# easyeda.net
KiCad netlist of a schematic drawn in EasyEDA
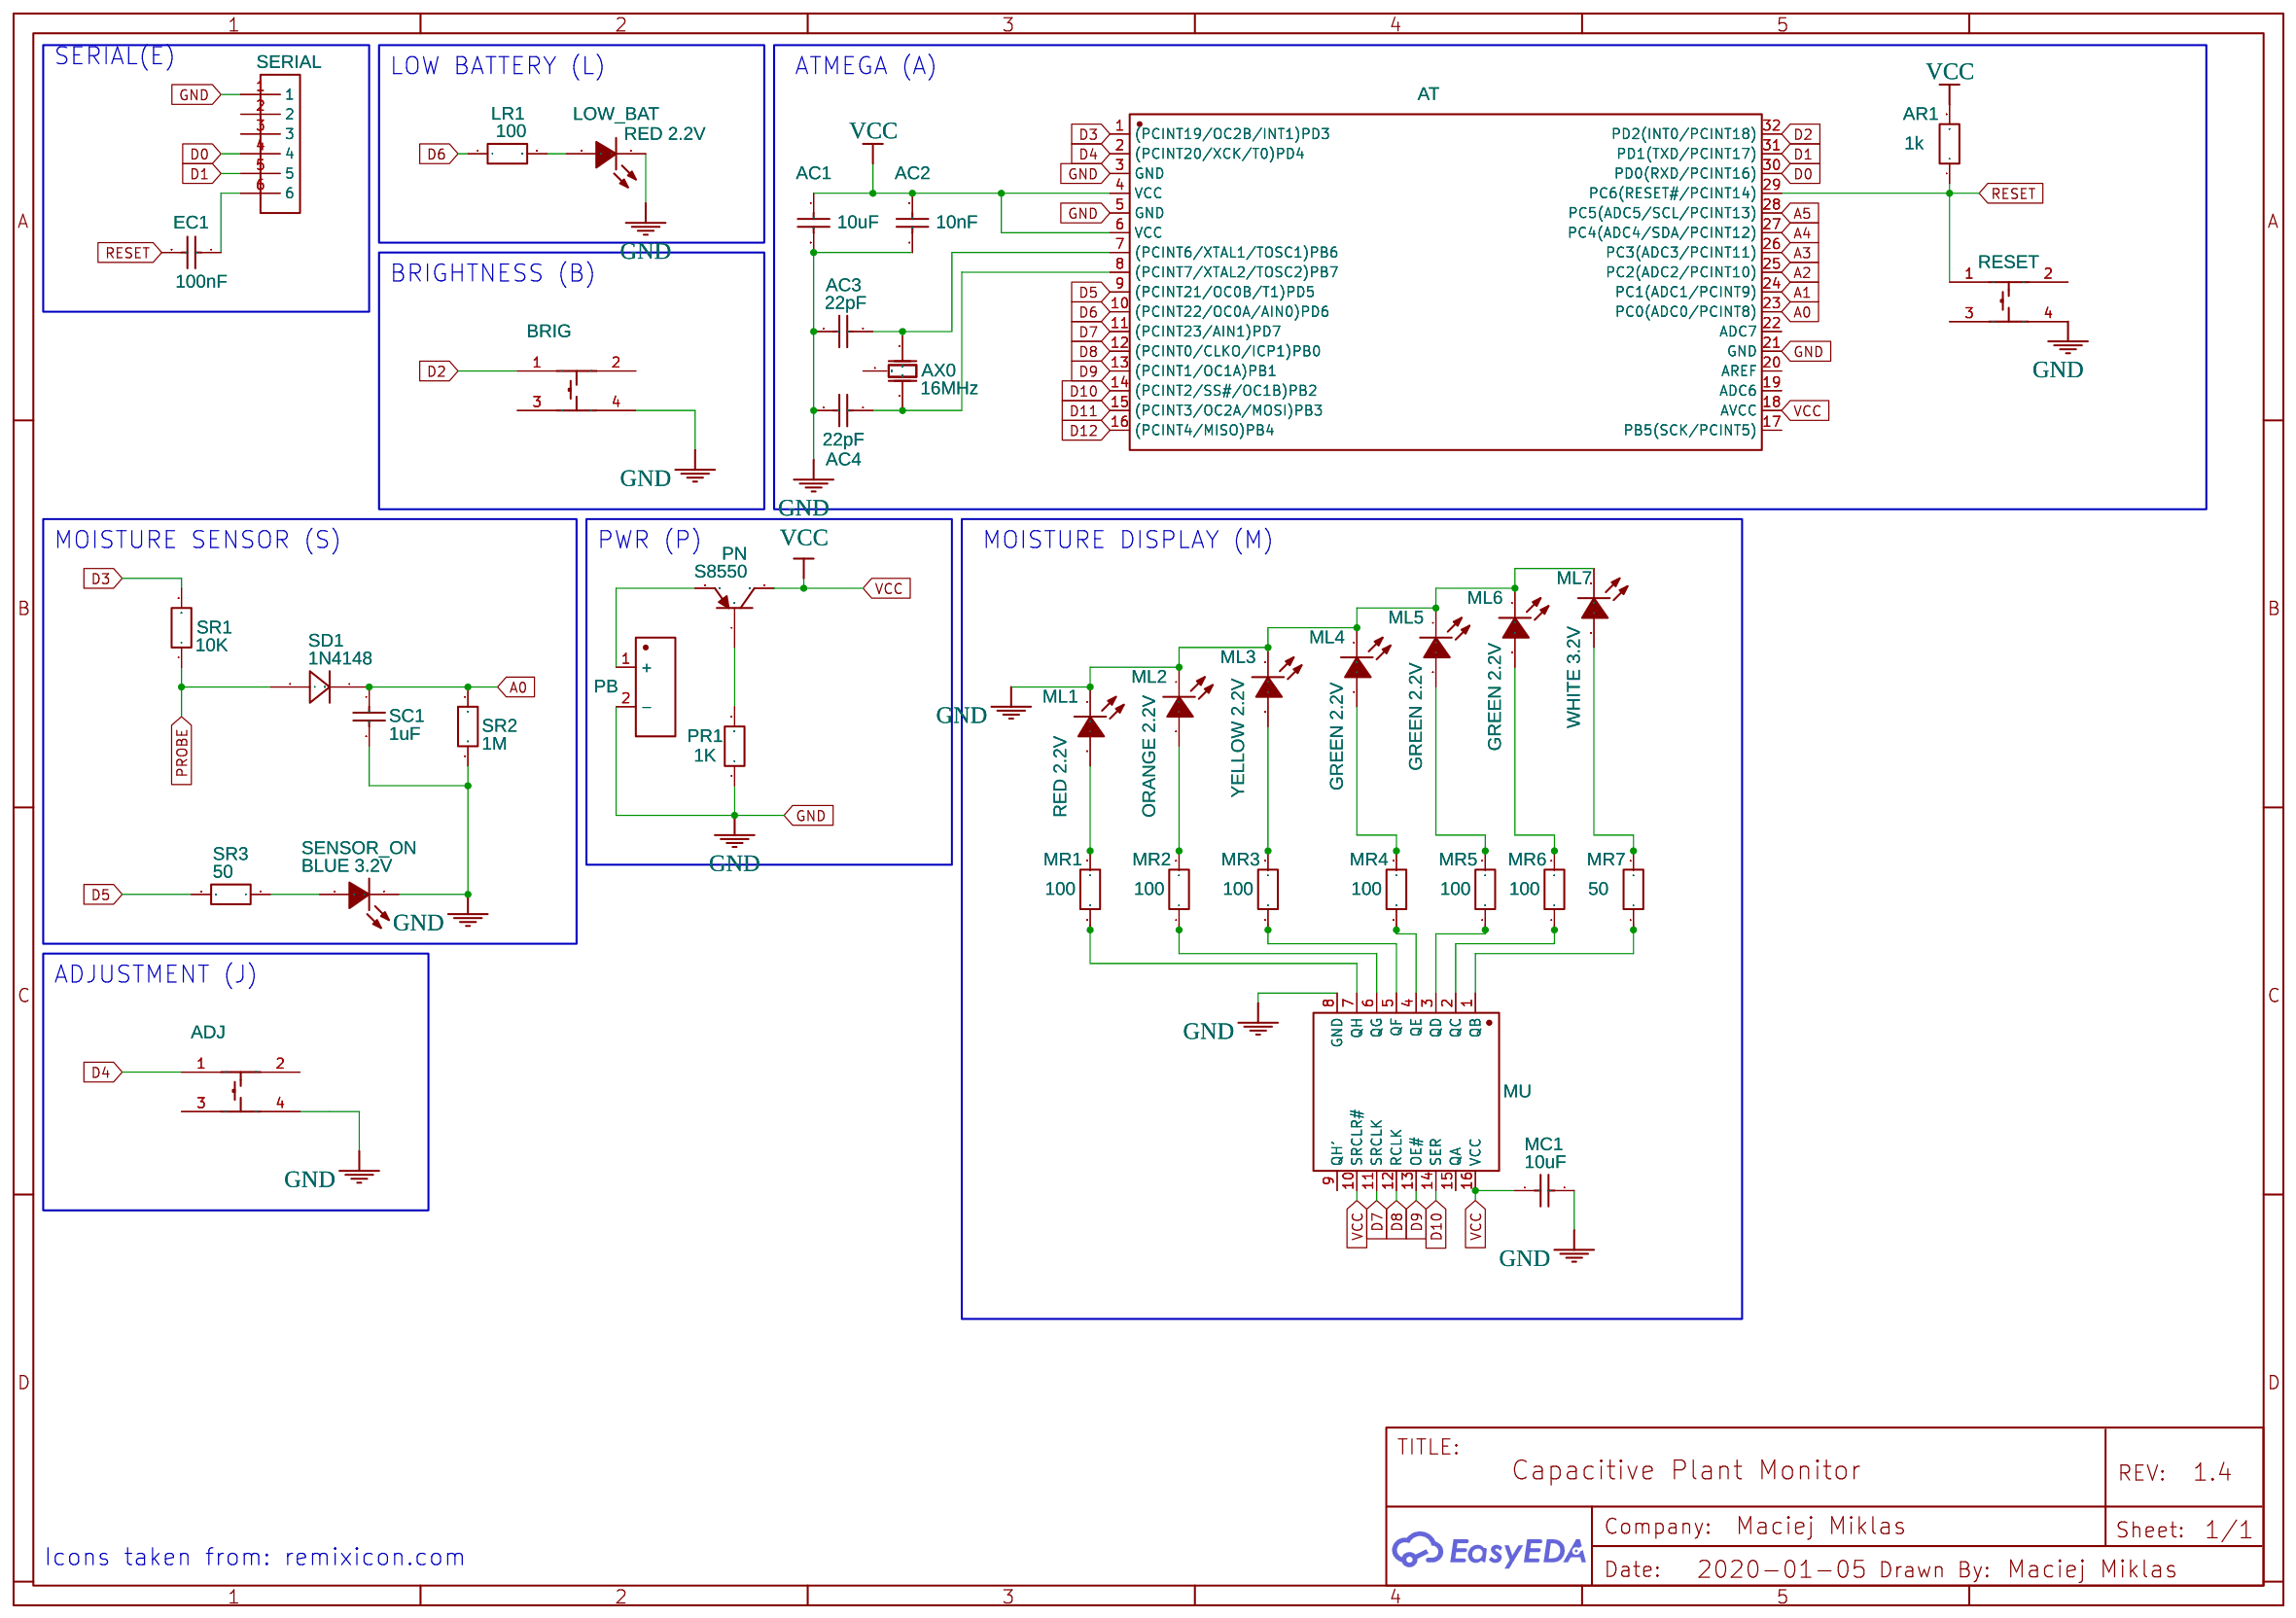
[diagram p0: schematic sheet]

(export (version "E")
  (design (tool "Eeschema 10.0.6"))
  (components
    (comp (ref "AC1")
      (value "10uF")
      (fields (field (name "Manufacturer Part") "CC0805KKX7R9BB105") (field (name "Manufacturer") "YAGEO"))
      (libsource (lib "") (part "CC0805KKX7R9BB105_1"))
    )
    (comp (ref "AC2")
      (value "10nF")
      (fields (field (name "Manufacturer Part") "CC0805KKX7R9BB105") (field (name "Manufacturer") "YAGEO"))
      (libsource (lib "") (part "CC0805KKX7R9BB105_1"))
    )
    (comp (ref "AC3")
      (value "22pF")
      (fields (field (name "Manufacturer Part") "CC0805KKX7R9BB105") (field (name "Manufacturer") "YAGEO"))
      (libsource (lib "") (part "CC0805KKX7R9BB105_2"))
    )
    (comp (ref "AC4")
      (value "22pF")
      (fields (field (name "Manufacturer Part") "CC0805KKX7R9BB105") (field (name "Manufacturer") "YAGEO"))
      (libsource (lib "") (part "CC0805KKX7R9BB105_2"))
    )
    (comp (ref "ADJ") (value "Push Button") (libsource (lib "") (part "Push Button")))
    (comp (ref "AR1")
      (value "1k")
      (fields
        (field (name "Manufacturer Part") "WR08X102 JTL")
        (field (name "Manufacturer") "Walsin Tech Corp")
      )
      (libsource (lib "") (part "WR08X102 JTL_2"))
    )
    (comp (ref "AT")
      (value "ATMEGA328P-AU")
      (fields (field (name "Manufacturer") "MICROCHIP"))
      (libsource (lib "") (part "ATMEGA328P-AU"))
    )
    (comp (ref "AX0")
      (value "16MHz")
      (fields
        (field (name "Manufacturer Part") "CSTNE16M0V530000R0")
        (field (name "Manufacturer") "Murata Electronics")
      )
      (libsource (lib "") (part "CSTNE16M0V530000R0"))
    )
    (comp (ref "BRIG") (value "Push Button") (libsource (lib "") (part "Push Button_2")))
    (comp (ref "EC1")
      (value "100nF")
      (fields (field (name "Manufacturer Part") "CC0805KKX7R9BB105") (field (name "Manufacturer") "YAGEO"))
      (libsource (lib "") (part "CC0805KKX7R9BB105"))
    )
    (comp (ref "LOW_BAT")
      (value "RED 2.2V")
      (fields
        (field (name "Manufacturer Part") "FC-1608YOXK-600H08")
        (field (name "Manufacturer") "NATIONSTAR")
      )
      (libsource (lib "") (part "FC-1608YOXK-600H08_1"))
    )
    (comp (ref "LR1")
      (value "100")
      (fields
        (field (name "Manufacturer Part") "WR08X102 JTL")
        (field (name "Manufacturer") "Walsin Tech Corp")
      )
      (libsource (lib "") (part "WR08X102 JTL_6"))
    )
    (comp (ref "MC1")
      (value "10uF")
      (fields (field (name "Manufacturer Part") "CC0805KKX7R9BB105") (field (name "Manufacturer") "YAGEO"))
      (libsource (lib "") (part "CC0805KKX7R9BB105_4"))
    )
    (comp (ref "ML1")
      (value "RED 2.2V")
      (fields
        (field (name "Manufacturer Part") "FC-1608YOXK-600H08")
        (field (name "Manufacturer") "NATIONSTAR")
      )
      (libsource (lib "") (part "FC-1608YOXK-600H08"))
    )
    (comp (ref "ML2")
      (value "ORANGE 2.2V")
      (fields
        (field (name "Manufacturer Part") "FC-1608YOXK-600H08")
        (field (name "Manufacturer") "NATIONSTAR")
      )
      (libsource (lib "") (part "FC-1608YOXK-600H08"))
    )
    (comp (ref "ML3")
      (value "YELLOW 2.2V")
      (fields
        (field (name "Manufacturer Part") "FC-1608YOXK-600H08")
        (field (name "Manufacturer") "NATIONSTAR")
      )
      (libsource (lib "") (part "FC-1608YOXK-600H08"))
    )
    (comp (ref "ML4")
      (value "GREEN 2.2V")
      (fields
        (field (name "Manufacturer Part") "FC-1608YOXK-600H08")
        (field (name "Manufacturer") "NATIONSTAR")
      )
      (libsource (lib "") (part "FC-1608YOXK-600H08"))
    )
    (comp (ref "ML5")
      (value "GREEN 2.2V")
      (fields
        (field (name "Manufacturer Part") "FC-1608YOXK-600H08")
        (field (name "Manufacturer") "NATIONSTAR")
      )
      (libsource (lib "") (part "FC-1608YOXK-600H08"))
    )
    (comp (ref "ML6")
      (value "GREEN 2.2V")
      (fields
        (field (name "Manufacturer Part") "FC-1608YOXK-600H08")
        (field (name "Manufacturer") "NATIONSTAR")
      )
      (libsource (lib "") (part "FC-1608YOXK-600H08"))
    )
    (comp (ref "ML7")
      (value "WHITE 3.2V")
      (fields
        (field (name "Manufacturer Part") "FC-1608YOXK-600H08")
        (field (name "Manufacturer") "NATIONSTAR")
      )
      (libsource (lib "") (part "FC-1608YOXK-600H08"))
    )
    (comp (ref "MR1")
      (value "100")
      (fields
        (field (name "Manufacturer Part") "WR08X102 JTL")
        (field (name "Manufacturer") "Walsin Tech Corp")
      )
      (libsource (lib "") (part "WR08X102 JTL_1"))
    )
    (comp (ref "MR2")
      (value "100")
      (fields
        (field (name "Manufacturer Part") "WR08X102 JTL")
        (field (name "Manufacturer") "Walsin Tech Corp")
      )
      (libsource (lib "") (part "WR08X102 JTL_1"))
    )
    (comp (ref "MR3")
      (value "100")
      (fields
        (field (name "Manufacturer Part") "WR08X102 JTL")
        (field (name "Manufacturer") "Walsin Tech Corp")
      )
      (libsource (lib "") (part "WR08X102 JTL_1"))
    )
    (comp (ref "MR4")
      (value "100")
      (fields
        (field (name "Manufacturer Part") "WR08X102 JTL")
        (field (name "Manufacturer") "Walsin Tech Corp")
      )
      (libsource (lib "") (part "WR08X102 JTL_1"))
    )
    (comp (ref "MR5")
      (value "100")
      (fields
        (field (name "Manufacturer Part") "WR08X102 JTL")
        (field (name "Manufacturer") "Walsin Tech Corp")
      )
      (libsource (lib "") (part "WR08X102 JTL_1"))
    )
    (comp (ref "MR6")
      (value "100")
      (fields
        (field (name "Manufacturer Part") "WR08X102 JTL")
        (field (name "Manufacturer") "Walsin Tech Corp")
      )
      (libsource (lib "") (part "WR08X102 JTL_1"))
    )
    (comp (ref "MR7")
      (value "50")
      (fields
        (field (name "Manufacturer Part") "WR08X102 JTL")
        (field (name "Manufacturer") "Walsin Tech Corp")
      )
      (libsource (lib "") (part "WR08X102 JTL_1"))
    )
    (comp (ref "MU")
      (value "CD74HC595M96")
      (fields (field (name "Manufacturer") "TI"))
      (libsource (lib "") (part "CD74HC595M96"))
    )
    (comp (ref "PB")
      (value "‎BK-18650-PC2‎")
      (fields
        (field (name "Manufacturer Part") "BK-18650-PC2")
        (field (name "Manufacturer") "MPD (Memory Protection Devices)")
      )
      (libsource (lib "") (part "‎BK-18650-PC2‎"))
    )
    (comp (ref "PN")
      (value "S8550")
      (fields (field (name "Manufacturer") "CBI(创基)"))
      (libsource (lib "") (part "S8550_C2828467"))
    )
    (comp (ref "PR1")
      (value "1K")
      (fields
        (field (name "Manufacturer Part") "WR08X102 JTL")
        (field (name "Manufacturer") "Walsin Tech Corp")
      )
      (libsource (lib "") (part "WR08X102 JTL_3"))
    )
    (comp (ref "RESET") (value "Push Button") (libsource (lib "") (part "Push Button_1")))
    (comp (ref "SC1")
      (value "1uF")
      (fields (field (name "Manufacturer Part") "CC0805KKX7R9BB105") (field (name "Manufacturer") "YAGEO"))
      (libsource (lib "") (part "CC0805KKX7R9BB105_3"))
    )
    (comp (ref "SD1")
      (value "1N4148")
      (fields (field (name "Manufacturer Part") "1N4148W") (field (name "Manufacturer") "Tak Cheong"))
      (libsource (lib "") (part "1N4148W-C129216"))
    )
    (comp (ref "SENSOR_ON")
      (value "BLUE 3.2V")
      (fields
        (field (name "Manufacturer Part") "FC-1608YOXK-600H08")
        (field (name "Manufacturer") "NATIONSTAR")
      )
      (libsource (lib "") (part "FC-1608YOXK-600H08_2"))
    )
    (comp (ref "SERIAL") (value "SERIAL") (libsource (lib "") (part "2.54_6PIN")))
    (comp (ref "SR1")
      (value "10K")
      (fields
        (field (name "Manufacturer Part") "WR08X102 JTL")
        (field (name "Manufacturer") "Walsin Tech Corp")
      )
      (libsource (lib "") (part "WR08X102 JTL_5"))
    )
    (comp (ref "SR2")
      (value "1M")
      (fields
        (field (name "Manufacturer Part") "WR08X102 JTL")
        (field (name "Manufacturer") "Walsin Tech Corp")
      )
      (libsource (lib "") (part "WR08X102 JTL"))
    )
    (comp (ref "SR3")
      (value "50")
      (fields
        (field (name "Manufacturer Part") "WR08X102 JTL")
        (field (name "Manufacturer") "Walsin Tech Corp")
      )
      (libsource (lib "") (part "WR08X102 JTL_4"))
    )
  )
  (nets
    (net (code "1") (name "A0") (class "Default")
      (node (ref "AT") (pin "23") (pinfunction "PC0(ADC0/PCINT8)_23") (pintype "unspecified"))
      (node (ref "SC1") (pin "1") (pinfunction "1_1") (pintype "input"))
      (node (ref "SD1") (pin "1") (pinfunction "C_1") (pintype "unspecified"))
      (node (ref "SR2") (pin "1") (pinfunction "1_1") (pintype "unspecified"))
    )
    (net (code "2") (name "A1") (class "Default")
      (node (ref "AT") (pin "24") (pinfunction "PC1(ADC1/PCINT9)_24") (pintype "unspecified"))
    )
    (net (code "3") (name "A2") (class "Default")
      (node (ref "AT") (pin "25") (pinfunction "PC2(ADC2/PCINT10)_25") (pintype "unspecified"))
    )
    (net (code "4") (name "A3") (class "Default")
      (node (ref "AT") (pin "26") (pinfunction "PC3(ADC3/PCINT11)_26") (pintype "unspecified"))
    )
    (net (code "5") (name "A4") (class "Default")
      (node (ref "AT") (pin "27") (pinfunction "PC4(ADC4/SDA/PCINT12)_27") (pintype "unspecified"))
    )
    (net (code "6") (name "A5") (class "Default")
      (node (ref "AT") (pin "28") (pinfunction "PC5(ADC5/SCL/PCINT13)_28") (pintype "unspecified"))
    )
    (net (code "7") (name "D0") (class "Default")
      (node (ref "AT") (pin "30") (pinfunction "PD0(RXD/PCINT16)_30") (pintype "unspecified"))
      (node (ref "SERIAL") (pin "4") (pinfunction "4_4") (pintype "unspecified"))
    )
    (net (code "8") (name "D1") (class "Default")
      (node (ref "AT") (pin "31") (pinfunction "PD1(TXD/PCINT17)_31") (pintype "unspecified"))
      (node (ref "SERIAL") (pin "5") (pinfunction "5_5") (pintype "unspecified"))
    )
    (net (code "9") (name "D2") (class "Default")
      (node (ref "AT") (pin "32") (pinfunction "PD2(INT0/PCINT18)_32") (pintype "unspecified"))
      (node (ref "BRIG") (pin "1") (pinfunction "1_1") (pintype "unspecified"))
    )
    (net (code "10") (name "D3") (class "Default")
      (node (ref "AT") (pin "1") (pinfunction "(PCINT19/OC2B/INT1)PD3_1") (pintype "unspecified"))
      (node (ref "SR1") (pin "2") (pinfunction "2_2") (pintype "unspecified"))
    )
    (net (code "11") (name "D4") (class "Default")
      (node (ref "ADJ") (pin "1") (pinfunction "1_1") (pintype "unspecified"))
      (node (ref "AT") (pin "2") (pinfunction "(PCINT20/XCK/T0)PD4_2") (pintype "unspecified"))
    )
    (net (code "12") (name "D5") (class "Default")
      (node (ref "AT") (pin "9") (pinfunction "(PCINT21/OC0B/T1)PD5_9") (pintype "unspecified"))
      (node (ref "SR3") (pin "2") (pinfunction "2_2") (pintype "unspecified"))
    )
    (net (code "13") (name "D6") (class "Default")
      (node (ref "AT") (pin "10") (pinfunction "(PCINT22/OC0A/AIN0)PD6_10") (pintype "unspecified"))
      (node (ref "LR1") (pin "1") (pinfunction "1_1") (pintype "unspecified"))
    )
    (net (code "14") (name "D7") (class "Default")
      (node (ref "AT") (pin "11") (pinfunction "(PCINT23/AIN1)PD7_11") (pintype "unspecified"))
      (node (ref "MU") (pin "11") (pinfunction "SRCLK_11") (pintype "unspecified"))
    )
    (net (code "15") (name "D8") (class "Default")
      (node (ref "AT") (pin "12") (pinfunction "(PCINT0/CLKO/ICP1)PB0_12") (pintype "unspecified"))
      (node (ref "MU") (pin "12") (pinfunction "RCLK_12") (pintype "unspecified"))
    )
    (net (code "16") (name "D9") (class "Default")
      (node (ref "AT") (pin "13") (pinfunction "(PCINT1/OC1A)PB1_13") (pintype "unspecified"))
      (node (ref "MU") (pin "13") (pinfunction "OE#_13") (pintype "unspecified"))
    )
    (net (code "17") (name "D10") (class "Default")
      (node (ref "AT") (pin "14") (pinfunction "(PCINT2/SS#/OC1B)PB2_14") (pintype "unspecified"))
      (node (ref "MU") (pin "14") (pinfunction "SER_14") (pintype "unspecified"))
    )
    (net (code "18") (name "D11") (class "Default")
      (node (ref "AT") (pin "15") (pinfunction "(PCINT3/OC2A/MOSI)PB3_15") (pintype "unspecified"))
    )
    (net (code "19") (name "D12") (class "Default")
      (node (ref "AT") (pin "16") (pinfunction "(PCINT4/MISO)PB4_16") (pintype "unspecified"))
    )
    (net (code "20") (name "GND") (class "Default")
      (node (ref "AC1") (pin "2") (pinfunction "2_2") (pintype "input"))
      (node (ref "AC2") (pin "2") (pinfunction "2_2") (pintype "input"))
      (node (ref "AC3") (pin "1") (pinfunction "1_1") (pintype "input"))
      (node (ref "AC4") (pin "1") (pinfunction "1_1") (pintype "input"))
      (node (ref "ADJ") (pin "4") (pinfunction "4_4") (pintype "unspecified"))
      (node (ref "AT") (pin "21") (pinfunction "GND_21") (pintype "unspecified"))
      (node (ref "AT") (pin "3") (pinfunction "GND_3") (pintype "unspecified"))
      (node (ref "AT") (pin "5") (pinfunction "GND_5") (pintype "unspecified"))
      (node (ref "BRIG") (pin "4") (pinfunction "4_4") (pintype "unspecified"))
      (node (ref "LOW_BAT") (pin "1") (pinfunction "K_1") (pintype "unspecified"))
      (node (ref "MC1") (pin "2") (pinfunction "2_2") (pintype "input"))
      (node (ref "ML1") (pin "1") (pinfunction "K_1") (pintype "unspecified"))
      (node (ref "ML2") (pin "1") (pinfunction "K_1") (pintype "unspecified"))
      (node (ref "ML3") (pin "1") (pinfunction "K_1") (pintype "unspecified"))
      (node (ref "ML4") (pin "1") (pinfunction "K_1") (pintype "unspecified"))
      (node (ref "ML5") (pin "1") (pinfunction "K_1") (pintype "unspecified"))
      (node (ref "ML6") (pin "1") (pinfunction "K_1") (pintype "unspecified"))
      (node (ref "ML7") (pin "1") (pinfunction "K_1") (pintype "unspecified"))
      (node (ref "MU") (pin "8") (pinfunction "GND_8") (pintype "unspecified"))
      (node (ref "PB") (pin "2") (pinfunction "-_2") (pintype "unspecified"))
      (node (ref "PR1") (pin "1") (pinfunction "1_1") (pintype "unspecified"))
      (node (ref "RESET") (pin "4") (pinfunction "4_4") (pintype "unspecified"))
      (node (ref "SC1") (pin "2") (pinfunction "2_2") (pintype "input"))
      (node (ref "SENSOR_ON") (pin "1") (pinfunction "K_1") (pintype "unspecified"))
      (node (ref "SERIAL") (pin "1") (pinfunction "1_1") (pintype "unspecified"))
      (node (ref "SR2") (pin "2") (pinfunction "2_2") (pintype "unspecified"))
    )
    (net (code "21") (name "Net-(AT-(PCINT6{slash}XTAL1{slash}TOSC1)PB6)") (class "Default")
      (node (ref "AC3") (pin "2") (pinfunction "2_2") (pintype "input"))
      (node (ref "AT") (pin "7") (pinfunction "(PCINT6/XTAL1/TOSC1)PB6_7") (pintype "unspecified"))
      (node (ref "AX0") (pin "3") (pinfunction "OSC2_3") (pintype "input"))
    )
    (net (code "22") (name "Net-(AT-(PCINT7{slash}XTAL2{slash}TOSC2)PB7)") (class "Default")
      (node (ref "AC4") (pin "2") (pinfunction "2_2") (pintype "input"))
      (node (ref "AT") (pin "8") (pinfunction "(PCINT7/XTAL2/TOSC2)PB7_8") (pintype "unspecified"))
      (node (ref "AX0") (pin "1") (pinfunction "OSC1_1") (pintype "input"))
    )
    (net (code "23") (name "Net-(EC1-Pad1)") (class "Default")
      (node (ref "EC1") (pin "1") (pinfunction "1_1") (pintype "input"))
      (node (ref "SERIAL") (pin "6") (pinfunction "6_6") (pintype "unspecified"))
    )
    (net (code "24") (name "Net-(LOW_BAT-A)") (class "Default")
      (node (ref "LOW_BAT") (pin "2") (pinfunction "A_2") (pintype "unspecified"))
      (node (ref "LR1") (pin "2") (pinfunction "2_2") (pintype "unspecified"))
    )
    (net (code "25") (name "Net-(ML1-A)") (class "Default")
      (node (ref "ML1") (pin "2") (pinfunction "A_2") (pintype "unspecified"))
      (node (ref "MR1") (pin "2") (pinfunction "2_2") (pintype "unspecified"))
    )
    (net (code "26") (name "Net-(ML2-A)") (class "Default")
      (node (ref "ML2") (pin "2") (pinfunction "A_2") (pintype "unspecified"))
      (node (ref "MR2") (pin "2") (pinfunction "2_2") (pintype "unspecified"))
    )
    (net (code "27") (name "Net-(ML3-A)") (class "Default")
      (node (ref "ML3") (pin "2") (pinfunction "A_2") (pintype "unspecified"))
      (node (ref "MR3") (pin "2") (pinfunction "2_2") (pintype "unspecified"))
    )
    (net (code "28") (name "Net-(ML4-A)") (class "Default")
      (node (ref "ML4") (pin "2") (pinfunction "A_2") (pintype "unspecified"))
      (node (ref "MR4") (pin "2") (pinfunction "2_2") (pintype "unspecified"))
    )
    (net (code "29") (name "Net-(ML5-A)") (class "Default")
      (node (ref "ML5") (pin "2") (pinfunction "A_2") (pintype "unspecified"))
      (node (ref "MR5") (pin "2") (pinfunction "2_2") (pintype "unspecified"))
    )
    (net (code "30") (name "Net-(ML6-A)") (class "Default")
      (node (ref "ML6") (pin "2") (pinfunction "A_2") (pintype "unspecified"))
      (node (ref "MR6") (pin "2") (pinfunction "2_2") (pintype "unspecified"))
    )
    (net (code "31") (name "Net-(ML7-A)") (class "Default")
      (node (ref "ML7") (pin "2") (pinfunction "A_2") (pintype "unspecified"))
      (node (ref "MR7") (pin "2") (pinfunction "2_2") (pintype "unspecified"))
    )
    (net (code "32") (name "Net-(MU-QB)") (class "Default")
      (node (ref "MR7") (pin "1") (pinfunction "1_1") (pintype "unspecified"))
      (node (ref "MU") (pin "1") (pinfunction "QB_1") (pintype "unspecified"))
    )
    (net (code "33") (name "Net-(MU-QC)") (class "Default")
      (node (ref "MR6") (pin "1") (pinfunction "1_1") (pintype "unspecified"))
      (node (ref "MU") (pin "2") (pinfunction "QC_2") (pintype "unspecified"))
    )
    (net (code "34") (name "Net-(MU-QD)") (class "Default")
      (node (ref "MR5") (pin "1") (pinfunction "1_1") (pintype "unspecified"))
      (node (ref "MU") (pin "3") (pinfunction "QD_3") (pintype "unspecified"))
    )
    (net (code "35") (name "Net-(MU-QE)") (class "Default")
      (node (ref "MR4") (pin "1") (pinfunction "1_1") (pintype "unspecified"))
      (node (ref "MU") (pin "4") (pinfunction "QE_4") (pintype "unspecified"))
    )
    (net (code "36") (name "Net-(MU-QF)") (class "Default")
      (node (ref "MR3") (pin "1") (pinfunction "1_1") (pintype "unspecified"))
      (node (ref "MU") (pin "5") (pinfunction "QF_5") (pintype "unspecified"))
    )
    (net (code "37") (name "Net-(MU-QG)") (class "Default")
      (node (ref "MR2") (pin "1") (pinfunction "1_1") (pintype "unspecified"))
      (node (ref "MU") (pin "6") (pinfunction "QG_6") (pintype "unspecified"))
    )
    (net (code "38") (name "Net-(MU-QH)") (class "Default")
      (node (ref "MR1") (pin "1") (pinfunction "1_1") (pintype "unspecified"))
      (node (ref "MU") (pin "7") (pinfunction "QH_7") (pintype "unspecified"))
    )
    (net (code "39") (name "Net-(PB-+)") (class "Default")
      (node (ref "PB") (pin "1") (pinfunction "+_1") (pintype "unspecified"))
      (node (ref "PN") (pin "2") (pinfunction "E_2") (pintype "unspecified"))
    )
    (net (code "40") (name "Net-(PN-B)") (class "Default")
      (node (ref "PN") (pin "1") (pinfunction "B_1") (pintype "unspecified"))
      (node (ref "PR1") (pin "2") (pinfunction "2_2") (pintype "unspecified"))
    )
    (net (code "41") (name "Net-(SENSOR_ON-A)") (class "Default")
      (node (ref "SENSOR_ON") (pin "2") (pinfunction "A_2") (pintype "unspecified"))
      (node (ref "SR3") (pin "1") (pinfunction "1_1") (pintype "unspecified"))
    )
    (net (code "42") (name "PROBE") (class "Default")
      (node (ref "SD1") (pin "2") (pinfunction "A_2") (pintype "unspecified"))
      (node (ref "SR1") (pin "1") (pinfunction "1_1") (pintype "unspecified"))
    )
    (net (code "43") (name "RESET") (class "Default")
      (node (ref "AR1") (pin "1") (pinfunction "1_1") (pintype "unspecified"))
      (node (ref "AT") (pin "29") (pinfunction "PC6(RESET#/PCINT14)_29") (pintype "unspecified"))
      (node (ref "EC1") (pin "2") (pinfunction "2_2") (pintype "input"))
      (node (ref "RESET") (pin "1") (pinfunction "1_1") (pintype "unspecified"))
    )
    (net (code "44") (name "VCC") (class "Default")
      (node (ref "AC1") (pin "1") (pinfunction "1_1") (pintype "input"))
      (node (ref "AC2") (pin "1") (pinfunction "1_1") (pintype "input"))
      (node (ref "AR1") (pin "2") (pinfunction "2_2") (pintype "unspecified"))
      (node (ref "AT") (pin "18") (pinfunction "AVCC_18") (pintype "unspecified"))
      (node (ref "AT") (pin "4") (pinfunction "VCC_4") (pintype "unspecified"))
      (node (ref "AT") (pin "6") (pinfunction "VCC_6") (pintype "unspecified"))
      (node (ref "MC1") (pin "1") (pinfunction "1_1") (pintype "input"))
      (node (ref "MU") (pin "10") (pinfunction "SRCLR#_10") (pintype "unspecified"))
      (node (ref "MU") (pin "16") (pinfunction "VCC_16") (pintype "unspecified"))
      (node (ref "PN") (pin "3") (pinfunction "C_3") (pintype "unspecified"))
    )
    (net (code "45") (name "unconnected-(ADJ-Pad2)") (class "Default")
      (node (ref "ADJ") (pin "2") (pinfunction "2_2") (pintype "unspecified"))
    )
    (net (code "46") (name "unconnected-(ADJ-Pad3)") (class "Default")
      (node (ref "ADJ") (pin "3") (pinfunction "3_3") (pintype "unspecified"))
    )
    (net (code "47") (name "unconnected-(AT-ADC6-Pad19)") (class "Default")
      (node (ref "AT") (pin "19") (pinfunction "ADC6_19") (pintype "unspecified"))
    )
    (net (code "48") (name "unconnected-(AT-ADC7-Pad22)") (class "Default")
      (node (ref "AT") (pin "22") (pinfunction "ADC7_22") (pintype "unspecified"))
    )
    (net (code "49") (name "unconnected-(AT-AREF-Pad20)") (class "Default")
      (node (ref "AT") (pin "20") (pinfunction "AREF_20") (pintype "unspecified"))
    )
    (net (code "50") (name "unconnected-(AT-PB5(SCK{slash}PCINT5)-Pad17)") (class "Default")
      (node (ref "AT") (pin "17") (pinfunction "PB5(SCK/PCINT5)_17") (pintype "unspecified"))
    )
    (net (code "51") (name "unconnected-(AX0-GND-Pad2)") (class "Default")
      (node (ref "AX0") (pin "2") (pinfunction "GND_2") (pintype "input"))
    )
    (net (code "52") (name "unconnected-(BRIG-Pad2)") (class "Default")
      (node (ref "BRIG") (pin "2") (pinfunction "2_2") (pintype "unspecified"))
    )
    (net (code "53") (name "unconnected-(BRIG-Pad3)") (class "Default")
      (node (ref "BRIG") (pin "3") (pinfunction "3_3") (pintype "unspecified"))
    )
    (net (code "54") (name "unconnected-(MU-QA-Pad15)") (class "Default")
      (node (ref "MU") (pin "15") (pinfunction "QA_15") (pintype "unspecified"))
    )
    (net (code "55") (name "unconnected-(MU-QH’-Pad9)") (class "Default")
      (node (ref "MU") (pin "9") (pinfunction "QH’_9") (pintype "unspecified"))
    )
    (net (code "56") (name "unconnected-(RESET-Pad2)") (class "Default")
      (node (ref "RESET") (pin "2") (pinfunction "2_2") (pintype "unspecified"))
    )
    (net (code "57") (name "unconnected-(RESET-Pad3)") (class "Default")
      (node (ref "RESET") (pin "3") (pinfunction "3_3") (pintype "unspecified"))
    )
    (net (code "58") (name "unconnected-(SERIAL-Pad2)") (class "Default")
      (node (ref "SERIAL") (pin "2") (pinfunction "2_2") (pintype "unspecified"))
    )
    (net (code "59") (name "unconnected-(SERIAL-Pad3)") (class "Default")
      (node (ref "SERIAL") (pin "3") (pinfunction "3_3") (pintype "unspecified"))
    )
  )
)
